# power.net
KiCad netlist of a schematic drawn in Altium Designer
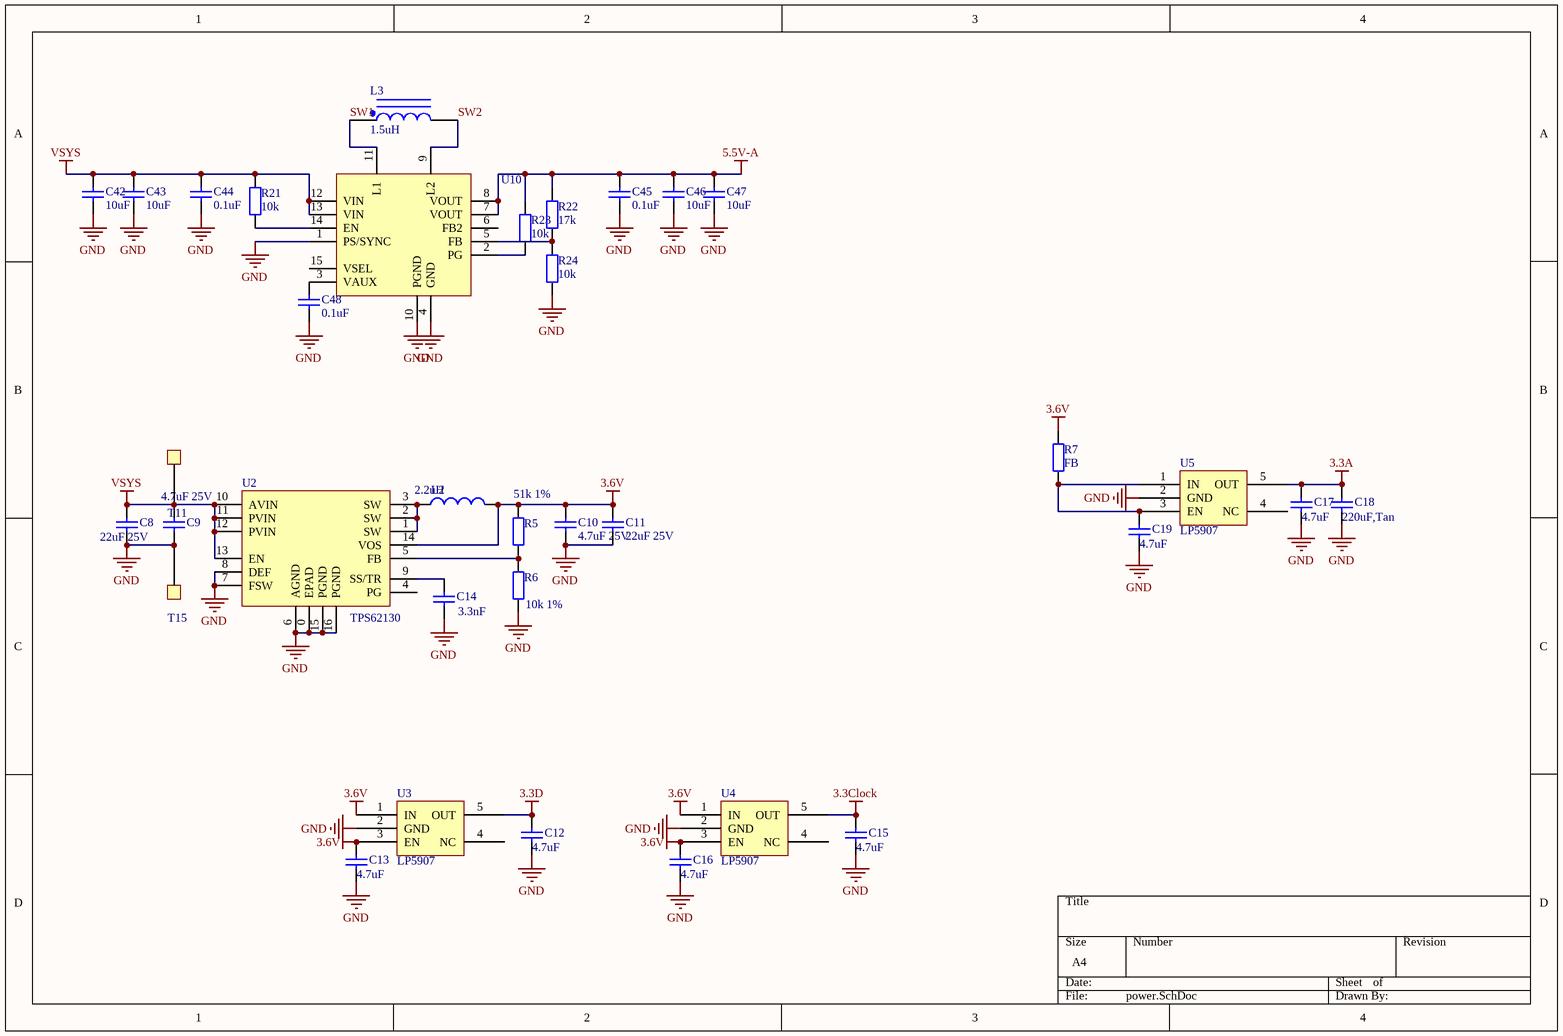
[diagram p0: power.SchDoc]

(export (version "E")
  (design (tool "Eeschema 10.0.6"))
  (components
    (comp (ref "C8")
      (value "22uF 25V")
      (footprint "0805")
      (description "Capacitor")
      (fields (field (name "Comment") "Cap") (field (name "PUBLISHER") "Altium Limited"))
      (libsource (lib "RTC6705") (part "Cap"))
    )
    (comp (ref "C9")
      (value "4.7uF 25V")
      (footprint "0603")
      (description "Capacitor")
      (fields (field (name "Comment") "Cap") (field (name "PUBLISHER") "Altium Limited"))
      (libsource (lib "RTC6705") (part "Cap"))
    )
    (comp (ref "C10")
      (value "4.7uF 25V")
      (footprint "0603")
      (description "Capacitor")
      (fields (field (name "Comment") "Cap") (field (name "PUBLISHER") "Altium Limited"))
      (libsource (lib "RTC6705") (part "Cap"))
    )
    (comp (ref "C11")
      (value "22uF 25V")
      (footprint "0805")
      (description "Capacitor")
      (fields (field (name "Comment") "Cap") (field (name "PUBLISHER") "Altium Limited"))
      (libsource (lib "RTC6705") (part "Cap"))
    )
    (comp (ref "C12")
      (value "4.7uF")
      (footprint "0603L")
      (description "Capacitor")
      (fields (field (name "PUBLISHER") "Altium Limited"))
      (libsource (lib "RTC6705") (part "Cap"))
    )
    (comp (ref "C13")
      (value "4.7uF")
      (footprint "0603L")
      (description "Capacitor")
      (fields (field (name "PUBLISHER") "Altium Limited"))
      (libsource (lib "RTC6705") (part "Cap"))
    )
    (comp (ref "C14")
      (value "3.3nF")
      (footprint "0402")
      (description "Capacitor")
      (fields (field (name "PUBLISHER") "Altium Limited"))
      (libsource (lib "RTC6705") (part "Cap"))
    )
    (comp (ref "C15")
      (value "4.7uF")
      (footprint "0603L")
      (description "Capacitor")
      (fields (field (name "PUBLISHER") "Altium Limited"))
      (libsource (lib "RTC6705") (part "Cap"))
    )
    (comp (ref "C16")
      (value "4.7uF")
      (footprint "0603L")
      (description "Capacitor")
      (fields (field (name "PUBLISHER") "Altium Limited"))
      (libsource (lib "RTC6705") (part "Cap"))
    )
    (comp (ref "C17")
      (value "4.7uF")
      (footprint "0603L")
      (description "Capacitor")
      (fields (field (name "PUBLISHER") "Altium Limited"))
      (libsource (lib "RTC6705") (part "Cap"))
    )
    (comp (ref "C18")
      (value "220uF,Tan")
      (footprint "1210")
      (description "Capacitor")
      (fields (field (name "PUBLISHER") "Altium Limited"))
      (libsource (lib "RTC6705") (part "Cap"))
    )
    (comp (ref "C19")
      (value "4.7uF")
      (footprint "0603L")
      (description "Capacitor")
      (fields (field (name "PUBLISHER") "Altium Limited"))
      (libsource (lib "RTC6705") (part "Cap"))
    )
    (comp (ref "C42")
      (value "10uF")
      (footprint "0805")
      (description "Capacitor")
      (fields (field (name "PUBLISHER") "Altium Limited"))
      (libsource (lib "RTC6705") (part "Cap"))
    )
    (comp (ref "C43")
      (value "10uF")
      (footprint "0805")
      (description "Capacitor")
      (fields (field (name "PUBLISHER") "Altium Limited"))
      (libsource (lib "RTC6705") (part "Cap"))
    )
    (comp (ref "C44")
      (value "0.1uF")
      (footprint "0603L")
      (description "Capacitor")
      (fields (field (name "PUBLISHER") "Altium Limited"))
      (libsource (lib "RTC6705") (part "Cap"))
    )
    (comp (ref "C45")
      (value "0.1uF")
      (footprint "0603L")
      (description "Capacitor")
      (fields (field (name "PUBLISHER") "Altium Limited"))
      (libsource (lib "RTC6705") (part "Cap"))
    )
    (comp (ref "C46")
      (value "10uF")
      (footprint "0805")
      (description "Capacitor")
      (fields (field (name "PUBLISHER") "Altium Limited"))
      (libsource (lib "RTC6705") (part "Cap"))
    )
    (comp (ref "C47")
      (value "10uF")
      (footprint "0805")
      (description "Capacitor")
      (fields (field (name "PUBLISHER") "Altium Limited"))
      (libsource (lib "RTC6705") (part "Cap"))
    )
    (comp (ref "C48")
      (value "0.1uF")
      (footprint "0402")
      (description "Capacitor")
      (fields (field (name "PUBLISHER") "Altium Limited"))
      (libsource (lib "RTC6705") (part "Cap"))
    )
    (comp (ref "L2")
      (value "2.2uH")
      (footprint "L4015")
      (description "Inductor")
      (fields (field (name "PUBLISHER") "Altium Limited"))
      (libsource (lib "Miscellaneous Devices") (part "Inductor"))
    )
    (comp (ref "L3")
      (value "1.5uH")
      (footprint "L4015")
      (description "Magnetic-Core Inductor with Winding Polarity Marking")
      (fields (field (name "PUBLISHER") "Altium Limited"))
      (libsource (lib "Miscellaneous Devices") (part "Inductor Iron Dot"))
    )
    (comp (ref "R5")
      (value "51k 1%")
      (footprint "0402")
      (description "Resistor")
      (fields (field (name "PUBLISHER") "Altium Limited"))
      (libsource (lib "") (part "Res2_1"))
    )
    (comp (ref "R6")
      (value "10k 1%")
      (footprint "0402")
      (description "Resistor")
      (fields (field (name "PUBLISHER") "Altium Limited"))
      (libsource (lib "") (part "Res2_1"))
    )
    (comp (ref "R7")
      (value "FB")
      (footprint "0603L")
      (description "Resistor")
      (fields (field (name "PUBLISHER") "Altium Limited"))
      (libsource (lib "Miscellaneous Devices") (part "Res2"))
    )
    (comp (ref "R21")
      (value "10k")
      (footprint "0402")
      (description "Resistor")
      (fields (field (name "PUBLISHER") "Altium Limited"))
      (libsource (lib "RTC6705") (part "Res2"))
    )
    (comp (ref "R22")
      (value "17k")
      (footprint "0402")
      (description "Resistor")
      (fields (field (name "PUBLISHER") "Altium Limited"))
      (libsource (lib "RTC6705") (part "Res2"))
    )
    (comp (ref "R23")
      (value "10k")
      (footprint "0402")
      (description "Resistor")
      (fields (field (name "PUBLISHER") "Altium Limited"))
      (libsource (lib "RTC6705") (part "Res2"))
    )
    (comp (ref "R24")
      (value "10k")
      (footprint "0402")
      (description "Resistor")
      (fields (field (name "PUBLISHER") "Altium Limited"))
      (libsource (lib "RTC6705") (part "Res2"))
    )
    (comp (ref "T11") (value "TestPad") (footprint "TestPad") (libsource (lib "sch") (part "TestPad")))
    (comp (ref "T15") (value "TestPad") (footprint "TestPad") (libsource (lib "") (part "TestPad_1")))
    (comp (ref "U2") (value "TPS62130") (footprint "TPS62130") (libsource (lib "sch") (part "TPS62130")))
    (comp (ref "U3") (value "LP5907") (footprint "SOT23-5") (libsource (lib "RTC6705") (part "LP5907")))
    (comp (ref "U4") (value "LP5907") (footprint "SOT23-5") (libsource (lib "RTC6705") (part "LP5907")))
    (comp (ref "U5") (value "LP5907") (footprint "SOT23-5") (libsource (lib "RTC6705") (part "LP5907")))
    (comp (ref "U10")
      (value "tps63070")
      (footprint "TPS63070")
      (libsource (lib "tps63070") (part "tps63070"))
    )
  )
  (nets
    (net (code "1") (name "/SW1") (class "Default")
      (node (ref "L3") (pin "1") (pinfunction "1_1") (pintype "passive"))
      (node (ref "U10") (pin "11") (pinfunction "L1_11") (pintype "passive"))
    )
    (net (code "2") (name "/SW2") (class "Default")
      (node (ref "L3") (pin "2") (pinfunction "2_2") (pintype "passive"))
      (node (ref "U10") (pin "9") (pinfunction "L2_9") (pintype "passive"))
    )
    (net (code "3") (name "3.3A") (class "Default")
      (node (ref "C17") (pin "2") (pinfunction "2_2") (pintype "passive"))
      (node (ref "C18") (pin "2") (pinfunction "2_2") (pintype "passive"))
      (node (ref "U5") (pin "5") (pinfunction "OUT_5") (pintype "passive"))
    )
    (net (code "4") (name "3.3Clock") (class "Default")
      (node (ref "C15") (pin "2") (pinfunction "2_2") (pintype "passive"))
      (node (ref "U4") (pin "5") (pinfunction "OUT_5") (pintype "passive"))
    )
    (net (code "5") (name "3.3D") (class "Default")
      (node (ref "C12") (pin "2") (pinfunction "2_2") (pintype "passive"))
      (node (ref "U3") (pin "5") (pinfunction "OUT_5") (pintype "passive"))
    )
    (net (code "6") (name "3.6V") (class "Default")
      (node (ref "C10") (pin "2") (pinfunction "2_2") (pintype "passive"))
      (node (ref "C11") (pin "2") (pinfunction "2_2") (pintype "passive"))
      (node (ref "C13") (pin "2") (pinfunction "2_2") (pintype "passive"))
      (node (ref "C16") (pin "2") (pinfunction "2_2") (pintype "passive"))
      (node (ref "L2") (pin "2") (pinfunction "2_2") (pintype "passive"))
      (node (ref "R5") (pin "1") (pinfunction "1_1") (pintype "passive"))
      (node (ref "R7") (pin "2") (pinfunction "2_2") (pintype "passive"))
      (node (ref "U2") (pin "14") (pinfunction "VOS_14") (pintype "passive"))
      (node (ref "U3") (pin "1") (pinfunction "IN_1") (pintype "passive"))
      (node (ref "U3") (pin "3") (pinfunction "EN_3") (pintype "passive"))
      (node (ref "U4") (pin "1") (pinfunction "IN_1") (pintype "passive"))
      (node (ref "U4") (pin "3") (pinfunction "EN_3") (pintype "passive"))
    )
    (net (code "7") (name "5.5V-A") (class "Default")
      (node (ref "C45") (pin "2") (pinfunction "2_2") (pintype "passive"))
      (node (ref "C46") (pin "2") (pinfunction "2_2") (pintype "passive"))
      (node (ref "C47") (pin "2") (pinfunction "2_2") (pintype "passive"))
      (node (ref "R22") (pin "2") (pinfunction "2_2") (pintype "passive"))
      (node (ref "R23") (pin "2") (pinfunction "2_2") (pintype "passive"))
      (node (ref "U10") (pin "7") (pinfunction "VOUT_7") (pintype "passive"))
      (node (ref "U10") (pin "8") (pinfunction "VOUT_8") (pintype "passive"))
    )
    (net (code "8") (name "GND") (class "Default")
      (node (ref "C10") (pin "1") (pinfunction "1_1") (pintype "passive"))
      (node (ref "C11") (pin "1") (pinfunction "1_1") (pintype "passive"))
      (node (ref "C12") (pin "1") (pinfunction "1_1") (pintype "passive"))
      (node (ref "C13") (pin "1") (pinfunction "1_1") (pintype "passive"))
      (node (ref "C14") (pin "2") (pinfunction "2_2") (pintype "passive"))
      (node (ref "C15") (pin "1") (pinfunction "1_1") (pintype "passive"))
      (node (ref "C16") (pin "1") (pinfunction "1_1") (pintype "passive"))
      (node (ref "C17") (pin "1") (pinfunction "1_1") (pintype "passive"))
      (node (ref "C18") (pin "1") (pinfunction "1_1") (pintype "passive"))
      (node (ref "C19") (pin "1") (pinfunction "1_1") (pintype "passive"))
      (node (ref "C42") (pin "1") (pinfunction "1_1") (pintype "passive"))
      (node (ref "C43") (pin "1") (pinfunction "1_1") (pintype "passive"))
      (node (ref "C44") (pin "1") (pinfunction "1_1") (pintype "passive"))
      (node (ref "C45") (pin "1") (pinfunction "1_1") (pintype "passive"))
      (node (ref "C46") (pin "1") (pinfunction "1_1") (pintype "passive"))
      (node (ref "C47") (pin "1") (pinfunction "1_1") (pintype "passive"))
      (node (ref "C48") (pin "2") (pinfunction "2_2") (pintype "passive"))
      (node (ref "C8") (pin "2") (pinfunction "2_2") (pintype "passive"))
      (node (ref "C9") (pin "2") (pinfunction "2_2") (pintype "passive"))
      (node (ref "R24") (pin "1") (pinfunction "1_1") (pintype "passive"))
      (node (ref "R6") (pin "2") (pinfunction "2_2") (pintype "passive"))
      (node (ref "T15") (pin "1") (pinfunction "3_1") (pintype "passive"))
      (node (ref "U10") (pin "1") (pinfunction "PS/SYNC_1") (pintype "passive"))
      (node (ref "U10") (pin "10") (pinfunction "PGND_10") (pintype "passive"))
      (node (ref "U10") (pin "4") (pinfunction "GND_4") (pintype "passive"))
      (node (ref "U2") (pin "0") (pinfunction "EPAD_0") (pintype "passive"))
      (node (ref "U2") (pin "15") (pinfunction "PGND_15") (pintype "passive"))
      (node (ref "U2") (pin "16") (pinfunction "PGND_16") (pintype "passive"))
      (node (ref "U2") (pin "6") (pinfunction "AGND_6") (pintype "passive"))
      (node (ref "U2") (pin "7") (pinfunction "FSW_7") (pintype "passive"))
      (node (ref "U2") (pin "8") (pinfunction "DEF_8") (pintype "passive"))
      (node (ref "U3") (pin "2") (pinfunction "GND_2") (pintype "passive"))
      (node (ref "U4") (pin "2") (pinfunction "GND_2") (pintype "passive"))
      (node (ref "U5") (pin "2") (pinfunction "GND_2") (pintype "passive"))
    )
    (net (code "9") (name "Net-(L2-Pad1)") (class "Default")
      (node (ref "L2") (pin "1") (pinfunction "1_1") (pintype "passive"))
      (node (ref "U2") (pin "1") (pinfunction "SW_1") (pintype "passive"))
      (node (ref "U2") (pin "2") (pinfunction "SW_2") (pintype "passive"))
      (node (ref "U2") (pin "3") (pinfunction "SW_3") (pintype "passive"))
    )
    (net (code "10") (name "Net-(U2-FB)") (class "Default")
      (node (ref "R5") (pin "2") (pinfunction "2_2") (pintype "passive"))
      (node (ref "R6") (pin "1") (pinfunction "1_1") (pintype "passive"))
      (node (ref "U2") (pin "5") (pinfunction "FB_5") (pintype "passive"))
    )
    (net (code "11") (name "Net-(U2-SS{slash}TR)") (class "Default")
      (node (ref "C14") (pin "1") (pinfunction "1_1") (pintype "passive"))
      (node (ref "U2") (pin "9") (pinfunction "SS/TR_9") (pintype "passive"))
    )
    (net (code "12") (name "Net-(U5-EN)") (class "Default")
      (node (ref "C19") (pin "2") (pinfunction "2_2") (pintype "passive"))
      (node (ref "R7") (pin "1") (pinfunction "1_1") (pintype "passive"))
      (node (ref "U5") (pin "1") (pinfunction "IN_1") (pintype "passive"))
      (node (ref "U5") (pin "3") (pinfunction "EN_3") (pintype "passive"))
    )
    (net (code "13") (name "Net-(U10-EN)") (class "Default")
      (node (ref "R21") (pin "1") (pinfunction "1_1") (pintype "passive"))
      (node (ref "U10") (pin "14") (pinfunction "EN_14") (pintype "passive"))
    )
    (net (code "14") (name "Net-(U10-FB)") (class "Default")
      (node (ref "R22") (pin "1") (pinfunction "1_1") (pintype "passive"))
      (node (ref "R24") (pin "2") (pinfunction "2_2") (pintype "passive"))
      (node (ref "U10") (pin "5") (pinfunction "FB_5") (pintype "passive"))
    )
    (net (code "15") (name "Net-(U10-PG)") (class "Default")
      (node (ref "R23") (pin "1") (pinfunction "1_1") (pintype "passive"))
      (node (ref "U10") (pin "2") (pinfunction "PG_2") (pintype "passive"))
    )
    (net (code "16") (name "Net-(U10-VAUX)") (class "Default")
      (node (ref "C48") (pin "1") (pinfunction "1_1") (pintype "passive"))
      (node (ref "U10") (pin "3") (pinfunction "VAUX_3") (pintype "passive"))
    )
    (net (code "17") (name "VSYS") (class "Default")
      (node (ref "C42") (pin "2") (pinfunction "2_2") (pintype "passive"))
      (node (ref "C43") (pin "2") (pinfunction "2_2") (pintype "passive"))
      (node (ref "C44") (pin "2") (pinfunction "2_2") (pintype "passive"))
      (node (ref "C8") (pin "1") (pinfunction "1_1") (pintype "passive"))
      (node (ref "C9") (pin "1") (pinfunction "1_1") (pintype "passive"))
      (node (ref "R21") (pin "2") (pinfunction "2_2") (pintype "passive"))
      (node (ref "T11") (pin "1") (pinfunction "3_1") (pintype "passive"))
      (node (ref "U10") (pin "12") (pinfunction "VIN_12") (pintype "passive"))
      (node (ref "U10") (pin "13") (pinfunction "VIN_13") (pintype "passive"))
      (node (ref "U2") (pin "10") (pinfunction "AVIN_10") (pintype "passive"))
      (node (ref "U2") (pin "11") (pinfunction "PVIN_11") (pintype "passive"))
      (node (ref "U2") (pin "12") (pinfunction "PVIN_12") (pintype "passive"))
      (node (ref "U2") (pin "13") (pinfunction "EN_13") (pintype "passive"))
    )
    (net (code "18") (name "unconnected-(U2-PG-Pad4)") (class "Default")
      (node (ref "U2") (pin "4") (pinfunction "PG_4") (pintype "passive"))
    )
    (net (code "19") (name "unconnected-(U3-NC-Pad4)") (class "Default")
      (node (ref "U3") (pin "4") (pinfunction "NC_4") (pintype "passive"))
    )
    (net (code "20") (name "unconnected-(U4-NC-Pad4)") (class "Default")
      (node (ref "U4") (pin "4") (pinfunction "NC_4") (pintype "passive"))
    )
    (net (code "21") (name "unconnected-(U5-NC-Pad4)") (class "Default")
      (node (ref "U5") (pin "4") (pinfunction "NC_4") (pintype "passive"))
    )
    (net (code "22") (name "unconnected-(U10-FB2-Pad6)") (class "Default")
      (node (ref "U10") (pin "6") (pinfunction "FB2_6") (pintype "passive"))
    )
    (net (code "23") (name "unconnected-(U10-VSEL-Pad15)") (class "Default")
      (node (ref "U10") (pin "15") (pinfunction "VSEL_15") (pintype "passive"))
    )
  )
)
